# ELEC5550_Team_26_Driver___Receiver_Schem.net
KiCad netlist of a schematic drawn in Altium Designer
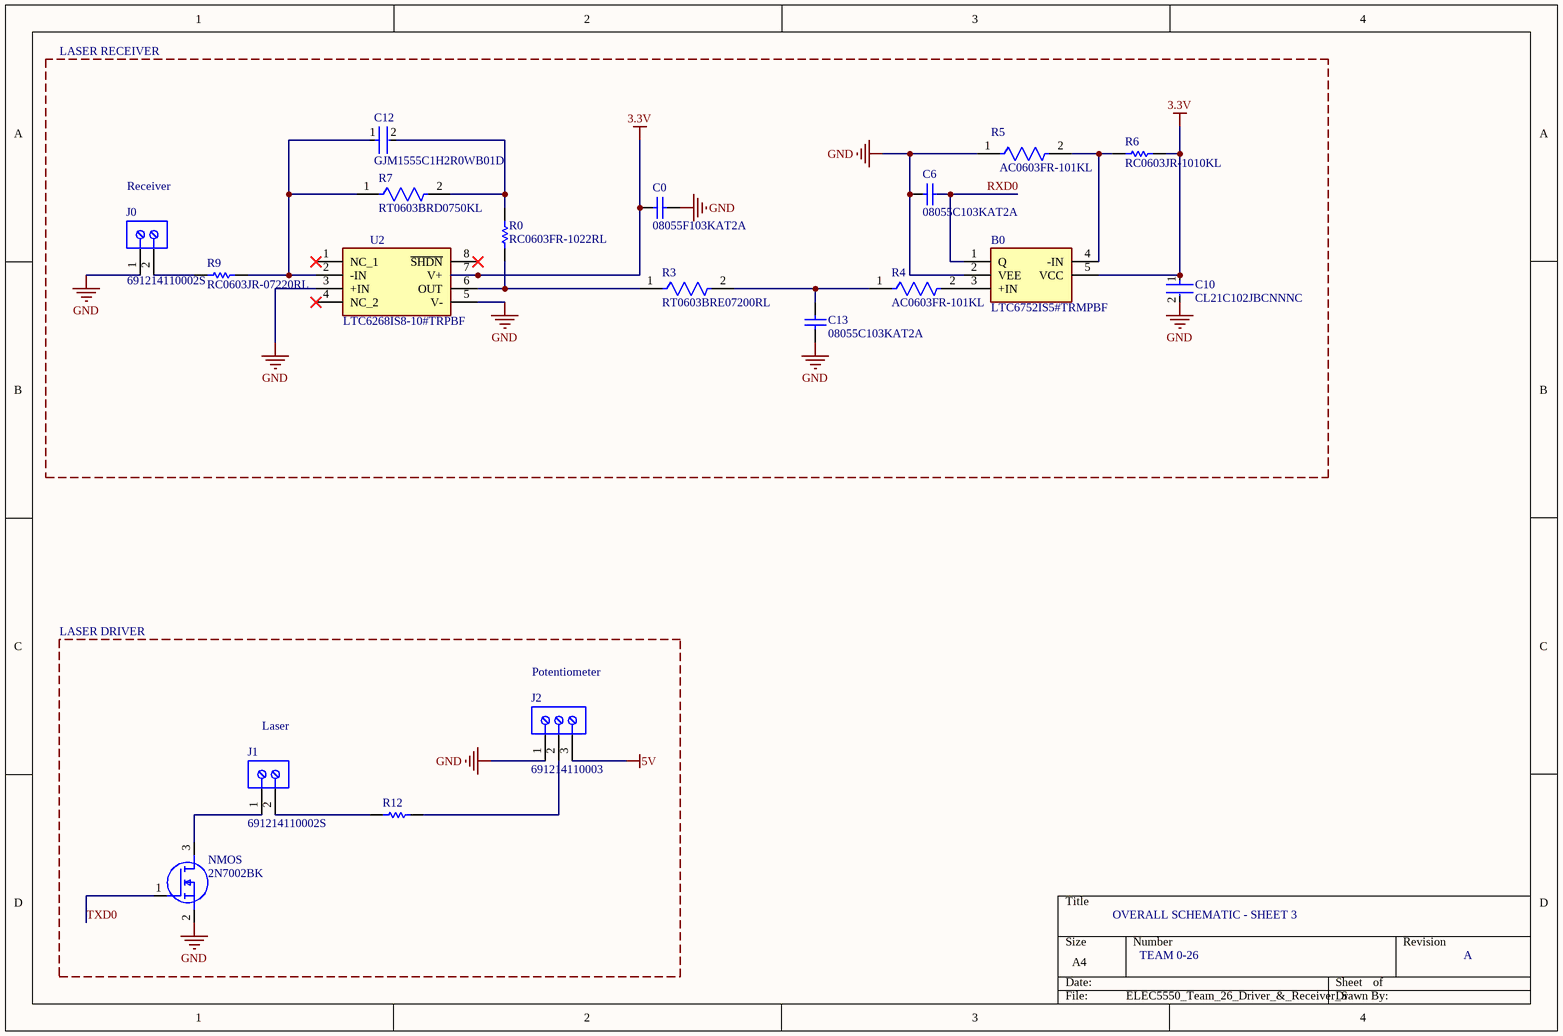
[diagram p0: ELEC5550_Team_26_Driver_&_Receiver_Schematic.SchDoc]

(export (version "E")
  (design (tool "Eeschema 10.0.6"))
  (components
    (comp (ref "B0")
      (value "LTC6752IS5#TRMPBF")
      (footprint "SOT95P280X100-5N")
      (fields (field (name "MOUSER PART NUMBER") "584-LTC6752IS5TRMPBF"))
      (libsource (lib "LTC6752IS5#TRMPBF") (part "LTC6752IS5#TRMPBF"))
    )
    (comp (ref "C0")
      (value "08055F103KAT2A")
      (footprint "CAPC2013X140X50LL20T25")
      (fields (field (name "MANUFACTURER") "AVX Interconnect / Elco"))
      (libsource (lib "Altium Content Vault") (part "CAP"))
    )
    (comp (ref "C6")
      (value "08055C103KAT2A")
      (footprint "CAPC2013X140X50LL20T25")
      (fields
        (field (name "PART NUMBER") "08055F103KAT2A")
        (field (name "MANUFACTURER") "AVX Interconnect / Elco")
      )
      (libsource (lib "Altium Content Vault") (part "CAP"))
    )
    (comp (ref "C10")
      (value "CL21C102JBCNNNC")
      (footprint "FP-C0805C-DN-MFG")
      (description "C0805 1,000 pF X7R 30ppm/°C 5.00% 50 V")
      (fields
        (field (name "OCTOPART") "https://octopart.com/c0805c102j5rac-kemet-1343162")
        (field (name "MANUFACTURER") "KEMET")
      )
      (libsource (lib "Altium Content Vault") (part "b4654b650e69147ec39a6b967a45e02"))
    )
    (comp (ref "C12")
      (value "GJM1555C1H2R0WB01D")
      (footprint "FP-GJM155-0_05-IPC_A")
      (description "Multi-Layer Ceramic Capacitor 2pF C0G  ±0.05pF 0402 Paper T/R")
      (libsource (lib "Altium Content Vault") (part "02cd4be3c70576c341d710602a673aa"))
    )
    (comp (ref "C13")
      (value "08055C103KAT2A")
      (footprint "CAPC2013X140X50LL20T25")
      (fields
        (field (name "PART NUMBER") "08055F103KAT2A")
        (field (name "MANUFACTURER") "AVX Interconnect / Elco")
      )
      (libsource (lib "Altium Content Vault") (part "CAP"))
    )
    (comp (ref "J0")
      (value "691214110002S")
      (footprint "691214110002S")
      (libsource (lib "Altium Content Vault") (part "TBL - 1R - 02P - Screw"))
    )
    (comp (ref "J1")
      (value "691214110002S")
      (footprint "691214110002S")
      (libsource (lib "Altium Content Vault") (part "TBL - 1R - 02P - Screw"))
    )
    (comp (ref "J2")
      (value "691214110003")
      (footprint "691214110003")
      (fields (field (name "VOLTAGE") "300V"))
      (libsource (lib "Altium Content Vault") (part "TBL - 1R - 03P - Screw"))
    )
    (comp (ref "NMOS")
      (value "2N7002BK")
      (footprint "SamacSys:TL431CDBZR215")
      (description "MOSFET (N-Channel)")
      (libsource (lib "*") (part "2N7002BK"))
    )
    (comp (ref "R0")
      (value "RC0603FR-1022RL")
      (footprint "RESC1608X55X25LL10T15")
      (fields (field (name "MANUFACTURER") "Yageo"))
      (libsource (lib "Altium Content Vault") (part "RES"))
    )
    (comp (ref "R3")
      (value "RT0603BRE07200RL")
      (footprint "FP-RT0603-MFG")
      (description "RES SMD 200 OHM 0.1% 1/10W 0603")
      (fields (field (name "MANUFACTURER") "Yageo") (field (name "TOLERANCE") "0.001"))
      (libsource (lib "Altium Content Vault") (part "1029c3af85768c4190bb7ad29bc67b5"))
    )
    (comp (ref "R4")
      (value "AC0603FR-101KL")
      (footprint "FP-AC0603-IPC_C")
      (description "RES 1kΩ 1.00% 0.1W 0603")
      (fields (field (name "TOLERANCE") "1%"))
      (libsource (lib "Altium Content Vault") (part "1029c3af85768c4190bb7ad29bc67b5"))
    )
    (comp (ref "R5")
      (value "AC0603FR-101KL")
      (footprint "FP-AC0603-IPC_C")
      (description "RES 1kΩ 1.00% 0.1W 0603")
      (fields (field (name "TOLERANCE") "1%"))
      (libsource (lib "Altium Content Vault") (part "1029c3af85768c4190bb7ad29bc67b5"))
    )
    (comp (ref "R6")
      (value "RC0603JR-1010KL")
      (footprint "RESC1608X55X25LL10T15")
      (fields (field (name "MANUFACTURER") "Yageo"))
      (libsource (lib "Altium Content Vault") (part "RES"))
    )
    (comp (ref "R7")
      (value "RT0603BRD0750KL")
      (footprint "FP-RT0603-0_55-MFG")
      (description "RES 50K OHM 0.1% 1/10W 0603")
      (libsource (lib "Altium Content Vault") (part "1029c3af85768c4190bb7ad29bc67b5"))
    )
    (comp (ref "R9")
      (value "RC0603JR-07220RL")
      (footprint "RESC1608X55X25LL10T15")
      (description "Chip Resistor, 220 Ohm, +/- 5%, 0.1 W, -55 to 155 degC, 0603 (1608 Metric), RoHS, Tape and Reel")
      (fields (field (name "TOLERANCE") "5%") (field (name "MANUFACTURER") "Yageo"))
      (libsource (lib "Altium Content Vault") (part "RES-2"))
    )
    (comp (ref "R12")
      (value "RC0603FR-07560RL")
      (footprint "RESC1608X55X25ML10T15")
      (description "Chip Resistor, 560 Ohm, +/- 1%, 0.1 W, -55 to 155 degC, 0603 (1608 Metric), RoHS, Tape and Reel")
      (fields (field (name "TOLERANCE") "1%"))
      (libsource (lib "Altium Content Vault") (part "RES-2"))
    )
    (comp (ref "U2")
      (value "LTC6268IS8-10#TRPBF")
      (footprint "SamacSys:SOIC127P599X175-8N")
      (description "Integrated Circuit")
      (fields (field (name "MOUSER PART NUMBER") "584-C6268IS8-10TRPBF"))
      (libsource (lib "*") (part "LTC6268IS8-10#TRPBF"))
    )
  )
  (nets
    (net (code "1") (name "/RXD0") (class "Default")
      (node (ref "B0") (pin "1") (pinfunction "Q_1") (pintype "passive"))
      (node (ref "C6") (pin "1") (pinfunction "1_1") (pintype "passive"))
    )
    (net (code "2") (name "/TXD0") (class "Default")
      (node (ref "NMOS") (pin "1") (pinfunction "G_1") (pintype "passive"))
    )
    (net (code "3") (name "3.3V") (class "Default")
      (node (ref "B0") (pin "5") (pinfunction "VCC_5") (pintype "passive"))
      (node (ref "C0") (pin "1") (pinfunction "1_1") (pintype "passive"))
      (node (ref "C10") (pin "1") (pinfunction "1_1") (pintype "passive"))
      (node (ref "R6") (pin "2") (pinfunction "2_2") (pintype "passive"))
      (node (ref "U2") (pin "7") (pinfunction "V+_7") (pintype "passive"))
    )
    (net (code "4") (name "5V") (class "Default")
      (node (ref "J2") (pin "3") (pinfunction "3_3") (pintype "passive"))
    )
    (net (code "5") (name "GND") (class "Default")
      (node (ref "B0") (pin "2") (pinfunction "VEE_2") (pintype "passive"))
      (node (ref "C0") (pin "2") (pinfunction "2_2") (pintype "passive"))
      (node (ref "C10") (pin "2") (pinfunction "2_2") (pintype "passive"))
      (node (ref "C13") (pin "1") (pinfunction "1_1") (pintype "passive"))
      (node (ref "C6") (pin "2") (pinfunction "2_2") (pintype "passive"))
      (node (ref "J0") (pin "1") (pinfunction "1_1") (pintype "passive"))
      (node (ref "J2") (pin "1") (pinfunction "1_1") (pintype "passive"))
      (node (ref "NMOS") (pin "2") (pinfunction "S_2") (pintype "passive"))
      (node (ref "R5") (pin "1") (pinfunction "1_1") (pintype "passive"))
      (node (ref "U2") (pin "3") (pinfunction "+IN_3") (pintype "passive"))
      (node (ref "U2") (pin "5") (pinfunction "V-_5") (pintype "passive"))
    )
    (net (code "6") (name "Net-(B0-+IN)") (class "Default")
      (node (ref "B0") (pin "3") (pinfunction "+IN_3") (pintype "passive"))
      (node (ref "R4") (pin "2") (pinfunction "2_2") (pintype "passive"))
    )
    (net (code "7") (name "Net-(B0--IN)") (class "Default")
      (node (ref "B0") (pin "4") (pinfunction "-IN_4") (pintype "passive"))
      (node (ref "R5") (pin "2") (pinfunction "2_2") (pintype "passive"))
      (node (ref "R6") (pin "1") (pinfunction "1_1") (pintype "passive"))
    )
    (net (code "8") (name "Net-(C12-Pad2)") (class "Default")
      (node (ref "C12") (pin "2") (pinfunction "2_2") (pintype "passive"))
      (node (ref "R0") (pin "2") (pinfunction "2_2") (pintype "passive"))
      (node (ref "R7") (pin "2") (pinfunction "2_2") (pintype "passive"))
    )
    (net (code "9") (name "Net-(C13-Pad2)") (class "Default")
      (node (ref "C13") (pin "2") (pinfunction "2_2") (pintype "passive"))
      (node (ref "R3") (pin "2") (pinfunction "2_2") (pintype "passive"))
      (node (ref "R4") (pin "1") (pinfunction "1_1") (pintype "passive"))
    )
    (net (code "10") (name "Net-(J0-Pad2)") (class "Default")
      (node (ref "J0") (pin "2") (pinfunction "2_2") (pintype "passive"))
      (node (ref "R9") (pin "1") (pinfunction "1_1") (pintype "passive"))
    )
    (net (code "11") (name "Net-(J1-Pad2)") (class "Default")
      (node (ref "J1") (pin "2") (pinfunction "2_2") (pintype "passive"))
      (node (ref "R12") (pin "1") (pinfunction "1_1") (pintype "passive"))
    )
    (net (code "12") (name "Net-(J2-Pad2)") (class "Default")
      (node (ref "J2") (pin "2") (pinfunction "2_2") (pintype "passive"))
      (node (ref "R12") (pin "2") (pinfunction "2_2") (pintype "passive"))
    )
    (net (code "13") (name "Net-(NMOS-D)") (class "Default")
      (node (ref "J1") (pin "1") (pinfunction "1_1") (pintype "passive"))
      (node (ref "NMOS") (pin "3") (pinfunction "D_3") (pintype "passive"))
    )
    (net (code "14") (name "Net-(U2--IN)") (class "Default")
      (node (ref "C12") (pin "1") (pinfunction "1_1") (pintype "passive"))
      (node (ref "R7") (pin "1") (pinfunction "1_1") (pintype "passive"))
      (node (ref "R9") (pin "2") (pinfunction "2_2") (pintype "passive"))
      (node (ref "U2") (pin "2") (pinfunction "-IN_2") (pintype "passive"))
    )
    (net (code "15") (name "Net-(U2-OUT)") (class "Default")
      (node (ref "R0") (pin "1") (pinfunction "1_1") (pintype "passive"))
      (node (ref "R3") (pin "1") (pinfunction "1_1") (pintype "passive"))
      (node (ref "U2") (pin "6") (pinfunction "OUT_6") (pintype "passive"))
    )
    (net (code "16") (name "unconnected-(U2-NC_1-Pad1)") (class "Default")
      (node (ref "U2") (pin "1") (pinfunction "NC_1_1") (pintype "passive+no_connect"))
    )
    (net (code "17") (name "unconnected-(U2-NC_2-Pad4)") (class "Default")
      (node (ref "U2") (pin "4") (pinfunction "NC_2_4") (pintype "passive+no_connect"))
    )
    (net (code "18") (name "unconnected-(U2-~{SHDN}-Pad8)") (class "Default")
      (node (ref "U2") (pin "8") (pinfunction "~{SHDN}_8") (pintype "passive+no_connect"))
    )
  )
)
